# lambda_bl49_v7.net
KiCad netlist of a schematic drawn in EAGLE
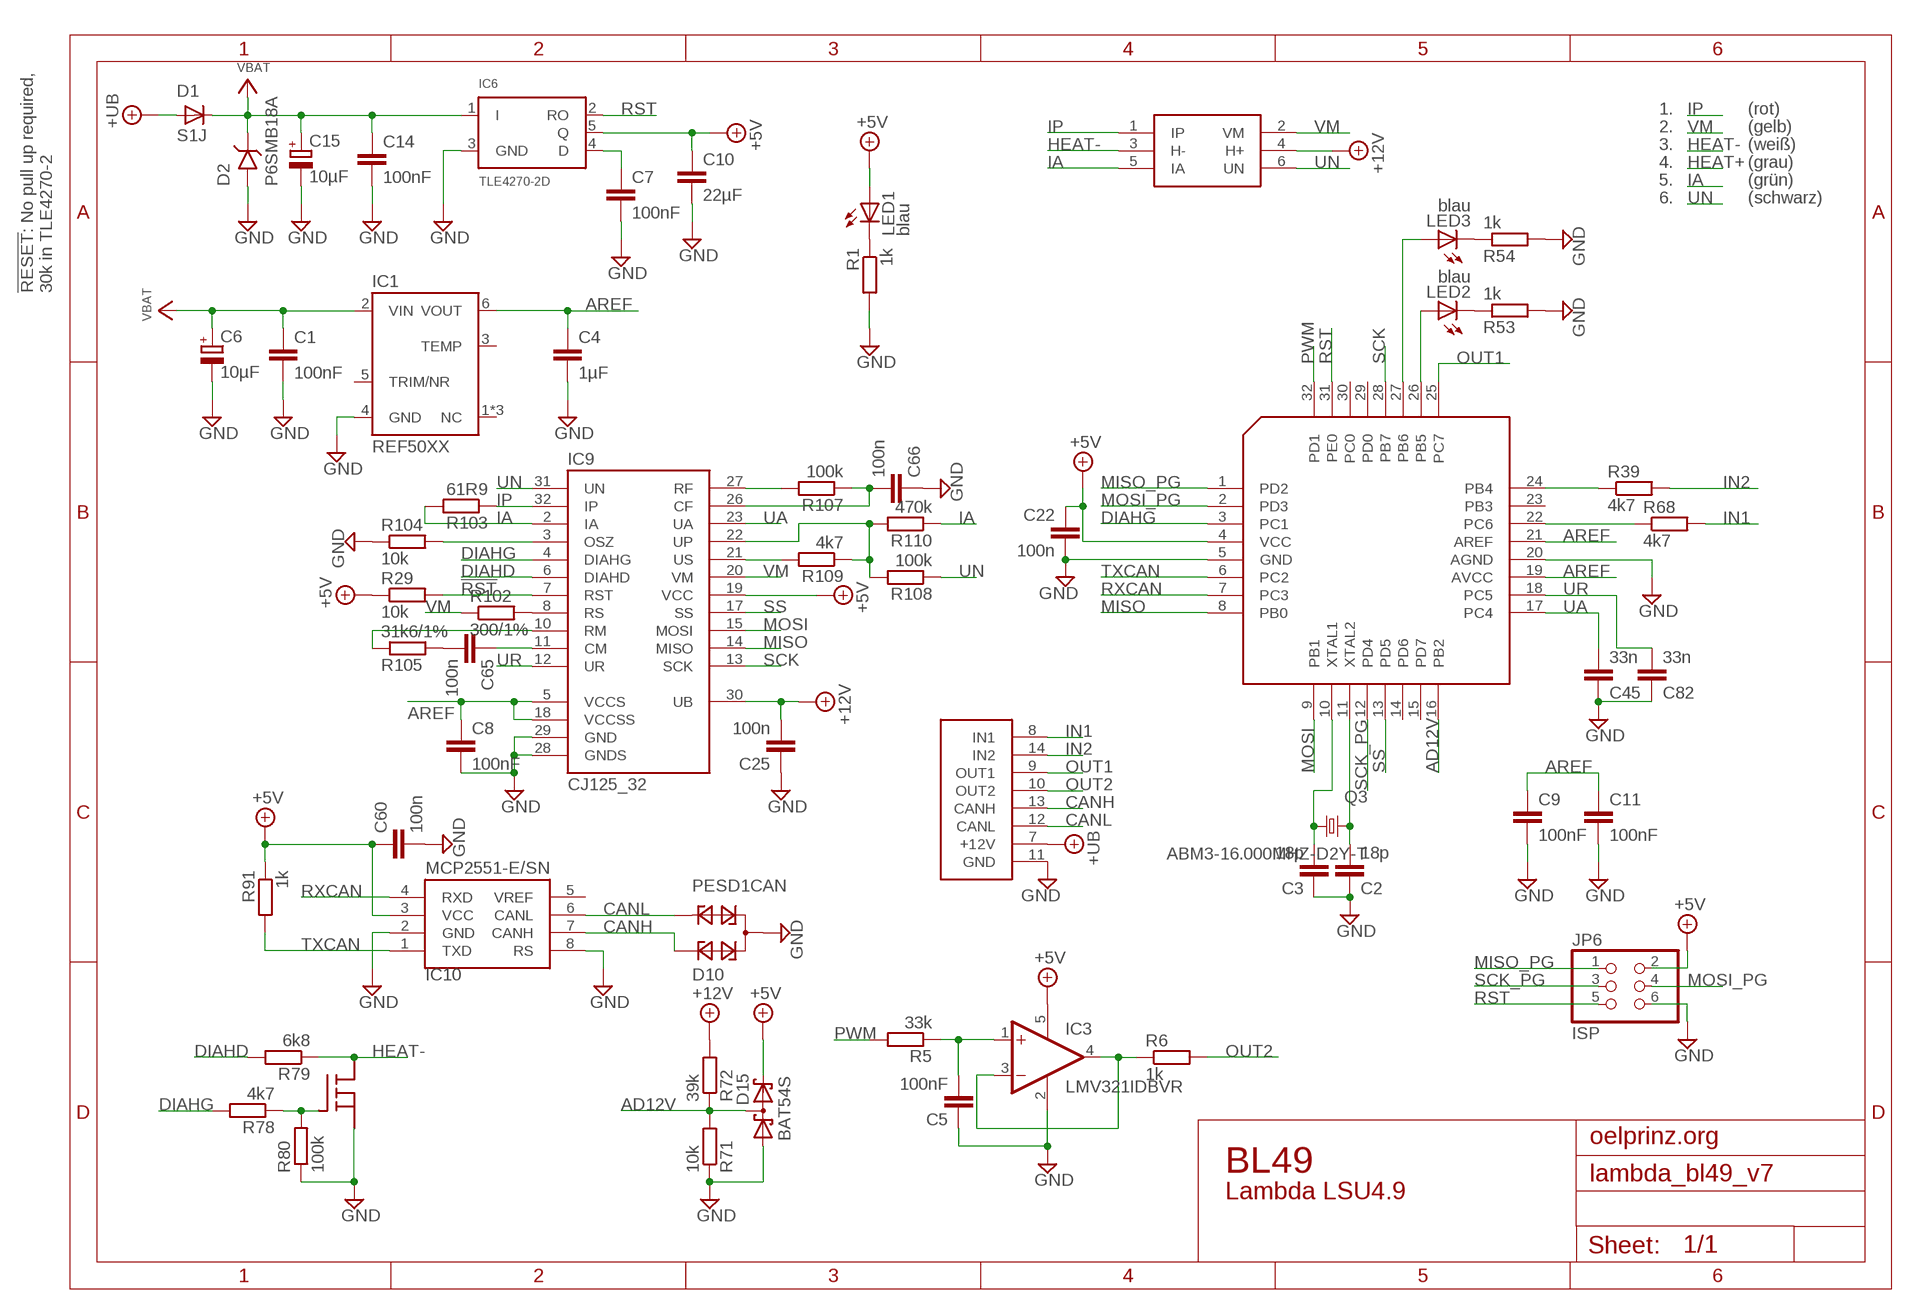
[diagram p0: schematic, sheet 1]

(export (version "E")
  (design (tool "Eeschema 10.0.6"))
  (components
    (comp (ref "C1")
      (value "100nF")
      (footprint "eagle-import:C0603")
      (libsource (lib "eagle-import") (part "rcl@1_C-EUC0603"))
    )
    (comp (ref "C2")
      (value "18p")
      (footprint "eagle-import:C0603")
      (libsource (lib "eagle-import") (part "C-EUC0603"))
    )
    (comp (ref "C3")
      (value "18p")
      (footprint "eagle-import:C0603")
      (libsource (lib "eagle-import") (part "C-EUC0603"))
    )
    (comp (ref "C4")
      (value "1µF")
      (footprint "eagle-import:C0603")
      (libsource (lib "eagle-import") (part "rcl@1_C-EUC0603"))
    )
    (comp (ref "C5")
      (value "100nF")
      (footprint "eagle-import:C0603")
      (libsource (lib "eagle-import") (part "C-EUC0603"))
    )
    (comp (ref "C6")
      (value "10µF")
      (footprint "eagle-import:PANASONIC_D")
      (libsource (lib "eagle-import") (part "CPOL-EUD"))
    )
    (comp (ref "C7")
      (value "100nF")
      (footprint "eagle-import:C0603")
      (libsource (lib "eagle-import") (part "rcl@1_C-EUC0603"))
    )
    (comp (ref "C8")
      (value "100nF")
      (footprint "eagle-import:C0603")
      (libsource (lib "eagle-import") (part "rcl@1_C-EUC0603"))
    )
    (comp (ref "C9")
      (value "100nF")
      (footprint "eagle-import:C0603")
      (libsource (lib "eagle-import") (part "rcl@1_C-EUC0603"))
    )
    (comp (ref "C10")
      (value "22µF")
      (footprint "eagle-import:C1206")
      (libsource (lib "eagle-import") (part "rcl@1_C-EUC1206"))
    )
    (comp (ref "C11")
      (value "100nF")
      (footprint "eagle-import:C0603")
      (libsource (lib "eagle-import") (part "rcl@1_C-EUC0603"))
    )
    (comp (ref "C14")
      (value "100nF")
      (footprint "eagle-import:C0603")
      (libsource (lib "eagle-import") (part "rcl@1_C-EUC0603"))
    )
    (comp (ref "C15")
      (value "10µF")
      (footprint "eagle-import:PANASONIC_D")
      (libsource (lib "eagle-import") (part "CPOL-EUD"))
    )
    (comp (ref "C22")
      (value "100n")
      (footprint "eagle-import:C0603")
      (libsource (lib "eagle-import") (part "C-EUC0603"))
    )
    (comp (ref "C25")
      (value "100n")
      (footprint "eagle-import:C0603")
      (libsource (lib "eagle-import") (part "rcl@1_C-EUC0603"))
    )
    (comp (ref "C45")
      (value "33n")
      (footprint "eagle-import:C0603")
      (libsource (lib "eagle-import") (part "C-EUC0603"))
    )
    (comp (ref "C60")
      (value "100n")
      (footprint "eagle-import:C0603")
      (libsource (lib "eagle-import") (part "C-EUC0603"))
    )
    (comp (ref "C65")
      (value "100n")
      (footprint "eagle-import:C0603")
      (libsource (lib "eagle-import") (part "C-EUC0603"))
    )
    (comp (ref "C66")
      (value "100n")
      (footprint "eagle-import:C0603")
      (libsource (lib "eagle-import") (part "C-EUC0603"))
    )
    (comp (ref "C82")
      (value "33n")
      (footprint "eagle-import:C0603")
      (libsource (lib "eagle-import") (part "C-EUC0603"))
    )
    (comp (ref "D1")
      (value "S1J")
      (footprint "eagle-import:SMADIODE")
      (libsource (lib "eagle-import") (part "DIODESMA"))
    )
    (comp (ref "D2")
      (value "P6SMB18A")
      (footprint "eagle-import:DO-214AA")
      (libsource (lib "eagle-import") (part "P6SMBXXASMB"))
    )
    (comp (ref "D10")
      (value "PESD1CAN")
      (footprint "eagle-import:SOT23")
      (libsource (lib "eagle-import") (part "PESD1CAN"))
    )
    (comp (ref "D15")
      (value "BAT54S")
      (footprint "eagle-import:SOT23")
      (libsource (lib "eagle-import") (part "BAT54S"))
    )
    (comp (ref "IC1")
      (value "REF50XX")
      (footprint "eagle-import:SOIC127P600X175-8N")
      (fields
        (field (name "MANUFACTURER_PART_NUMBER") "REF5050AIDR")
        (field (name "MOUSER_PART_NUMBER") "595-REF5050AIDR")
      )
      (libsource (lib "eagle-import") (part "REF50XX"))
    )
    (comp (ref "IC3")
      (value "LMV321IDBVR")
      (footprint "eagle-import:SC70-5L")
      (libsource (lib "eagle-import") (part "LMV321?M7"))
    )
    (comp (ref "IC6")
      (value "TLE4270-2D")
      (footprint "eagle-import:TO252-51")
      (libsource (lib "eagle-import") (part "TLE4270-2D"))
    )
    (comp (ref "IC9")
      (value "CJ125_32")
      (footprint "eagle-import:TQFP32-08")
      (libsource (lib "eagle-import") (part "CJ125_32"))
    )
    (comp (ref "IC10")
      (value "MCP2551-E/SN")
      (footprint "eagle-import:SOIC8")
      (libsource (lib "eagle-import") (part "MCP255"))
    )
    (comp (ref "JP6")
      (value "ISP")
      (footprint "eagle-import:2X03")
      (libsource (lib "eagle-import") (part "PINHD-2X3"))
    )
    (comp (ref "LED1")
      (value "blau")
      (footprint "eagle-import:SML0805")
      (libsource (lib "eagle-import") (part "LEDSML0805"))
    )
    (comp (ref "LED2")
      (value "blau")
      (footprint "eagle-import:SML0805")
      (libsource (lib "eagle-import") (part "LEDSML0805"))
    )
    (comp (ref "LED3")
      (value "blau")
      (footprint "eagle-import:SML0805")
      (libsource (lib "eagle-import") (part "LEDSML0805"))
    )
    (comp (ref "Q3")
      (value "ABM3-16.000MHZ-D2Y-T")
      (footprint "eagle-import:ABM3")
      (libsource (lib "eagle-import") (part "ABM3-8.000MHZ-D2Y-T"))
    )
    (comp (ref "R1")
      (value "1k")
      (footprint "eagle-import:R0603")
      (libsource (lib "eagle-import") (part "R-EU_R0603"))
    )
    (comp (ref "R5")
      (value "33k")
      (footprint "eagle-import:R0603")
      (libsource (lib "eagle-import") (part "R-EU_R0603"))
    )
    (comp (ref "R6")
      (value "1k")
      (footprint "eagle-import:R0603")
      (libsource (lib "eagle-import") (part "R-EU_R0603"))
    )
    (comp (ref "R29")
      (value "10k")
      (footprint "eagle-import:R0603")
      (libsource (lib "eagle-import") (part "R-EU_R0603"))
    )
    (comp (ref "R39")
      (value "4k7")
      (footprint "eagle-import:R0603")
      (libsource (lib "eagle-import") (part "R-EU_R0603"))
    )
    (comp (ref "R53")
      (value "1k")
      (footprint "eagle-import:R0603")
      (libsource (lib "eagle-import") (part "R-EU_R0603"))
    )
    (comp (ref "R54")
      (value "1k")
      (footprint "eagle-import:R0603")
      (libsource (lib "eagle-import") (part "R-EU_R0603"))
    )
    (comp (ref "R68")
      (value "4k7")
      (footprint "eagle-import:R0603")
      (libsource (lib "eagle-import") (part "R-EU_R0603"))
    )
    (comp (ref "R71")
      (value "10k")
      (footprint "eagle-import:R0603")
      (libsource (lib "eagle-import") (part "R-EU_R0603"))
    )
    (comp (ref "R72")
      (value "39k")
      (footprint "eagle-import:R0603")
      (libsource (lib "eagle-import") (part "R-EU_R0603"))
    )
    (comp (ref "R78")
      (value "4k7")
      (footprint "eagle-import:R0603")
      (libsource (lib "eagle-import") (part "R-EU_R0603"))
    )
    (comp (ref "R79")
      (value "6k8")
      (footprint "eagle-import:R0603")
      (libsource (lib "eagle-import") (part "R-EU_R0603"))
    )
    (comp (ref "R80")
      (value "100k")
      (footprint "eagle-import:R0603")
      (libsource (lib "eagle-import") (part "R-EU_R0603"))
    )
    (comp (ref "R91")
      (value "1k")
      (footprint "eagle-import:R0603")
      (libsource (lib "eagle-import") (part "R-EU_R0603"))
    )
    (comp (ref "R102")
      (value "300/1%")
      (footprint "eagle-import:R0603")
      (libsource (lib "eagle-import") (part "R-EU_R0603"))
    )
    (comp (ref "R103")
      (value "61R9")
      (footprint "eagle-import:R0603")
      (libsource (lib "eagle-import") (part "R-EU_R0603"))
    )
    (comp (ref "R104")
      (value "10k")
      (footprint "eagle-import:R0603")
      (libsource (lib "eagle-import") (part "R-EU_R0603"))
    )
    (comp (ref "R105")
      (value "31k6/1%")
      (footprint "eagle-import:R0603")
      (libsource (lib "eagle-import") (part "R-EU_R0603"))
    )
    (comp (ref "R107")
      (value "100k")
      (footprint "eagle-import:R0603")
      (libsource (lib "eagle-import") (part "R-EU_R0603"))
    )
    (comp (ref "R108")
      (value "100k")
      (footprint "eagle-import:R0603")
      (libsource (lib "eagle-import") (part "R-EU_R0603"))
    )
    (comp (ref "R109")
      (value "4k7")
      (footprint "eagle-import:R0603")
      (libsource (lib "eagle-import") (part "R-EU_R0603"))
    )
    (comp (ref "R110")
      (value "470k")
      (footprint "eagle-import:R0603")
      (libsource (lib "eagle-import") (part "R-EU_R0603"))
    )
    (comp (ref "U$1")
      (value "BL49")
      (footprint "eagle-import:BL49")
      (libsource (lib "eagle-import") (part "BL49"))
    )
    (comp (ref "U$2")
      (value "ATMEGA32M1-AU")
      (footprint "eagle-import:TQFP32-08")
      (libsource (lib "eagle-import") (part "AT32M1"))
    )
    (comp (ref "U$3")
      (value "STD30NF06LT4")
      (footprint "eagle-import:DPACK_2")
      (libsource (lib "eagle-import") (part "IRLZ44"))
    )
  )
  (nets
    (net (code "1") (name "+5V") (class "Default")
      (node (ref "C10") (pin "1") (pinfunction "1_1") (pintype "passive"))
      (node (ref "C22") (pin "1") (pinfunction "1_1") (pintype "passive"))
      (node (ref "C60") (pin "1") (pinfunction "1_1") (pintype "passive"))
      (node (ref "D15") (pin "2") (pinfunction "C2_2") (pintype "passive"))
      (node (ref "IC10") (pin "3") (pinfunction "VCC_3") (pintype "bidirectional"))
      (node (ref "IC3") (pin "5") (pinfunction "V+_5") (pintype "power_in"))
      (node (ref "IC6") (pin "5") (pinfunction "Q_5") (pintype "bidirectional"))
      (node (ref "IC9") (pin "19") (pinfunction "VCC_19") (pintype "bidirectional"))
      (node (ref "JP6") (pin "2") (pinfunction "2_2") (pintype "passive"))
      (node (ref "LED1") (pin "A") (pinfunction "A_A") (pintype "passive"))
      (node (ref "R29") (pin "1") (pinfunction "1_1") (pintype "passive"))
      (node (ref "R91") (pin "1") (pinfunction "1_1") (pintype "passive"))
      (node (ref "U$2") (pin "4") (pinfunction "VCC_4") (pintype "bidirectional"))
    )
    (net (code "2") (name "+12V") (class "Default")
      (node (ref "C25") (pin "2") (pinfunction "2_2") (pintype "passive"))
      (node (ref "IC9") (pin "30") (pinfunction "UB_30") (pintype "bidirectional"))
      (node (ref "R72") (pin "2") (pinfunction "2_2") (pintype "passive"))
      (node (ref "U$1") (pin "4") (pinfunction "H+_4") (pintype "bidirectional"))
    )
    (net (code "3") (name "+UB") (class "Default")
      (node (ref "D1") (pin "A") (pinfunction "A_A") (pintype "passive"))
      (node (ref "U$1") (pin "7") (pinfunction "+12V_7") (pintype "bidirectional"))
    )
    (net (code "4") (name "/AD12V") (class "Default")
      (node (ref "D15") (pin "3") (pinfunction "C1A2_3") (pintype "passive"))
      (node (ref "R71") (pin "2") (pinfunction "2_2") (pintype "passive"))
      (node (ref "R72") (pin "1") (pinfunction "1_1") (pintype "passive"))
      (node (ref "U$2") (pin "16") (pinfunction "PB2_16") (pintype "bidirectional"))
    )
    (net (code "5") (name "/AREF") (class "Default")
      (node (ref "C11") (pin "1") (pinfunction "1_1") (pintype "passive"))
      (node (ref "C4") (pin "1") (pinfunction "1_1") (pintype "passive"))
      (node (ref "C8") (pin "1") (pinfunction "1_1") (pintype "passive"))
      (node (ref "C9") (pin "1") (pinfunction "1_1") (pintype "passive"))
      (node (ref "IC1") (pin "6") (pinfunction "VOUT_6") (pintype "output"))
      (node (ref "IC9") (pin "18") (pinfunction "VCCSS_18") (pintype "bidirectional"))
      (node (ref "IC9") (pin "5") (pinfunction "VCCS_5") (pintype "bidirectional"))
      (node (ref "U$2") (pin "19") (pinfunction "AVCC_19") (pintype "bidirectional"))
      (node (ref "U$2") (pin "21") (pinfunction "AREF_21") (pintype "bidirectional"))
    )
    (net (code "6") (name "/CANH") (class "Default")
      (node (ref "D10") (pin "1") (pinfunction "1_1") (pintype "passive"))
      (node (ref "IC10") (pin "7") (pinfunction "CANH_7") (pintype "bidirectional"))
      (node (ref "U$1") (pin "13") (pinfunction "CANH_13") (pintype "bidirectional"))
    )
    (net (code "7") (name "/CANL") (class "Default")
      (node (ref "D10") (pin "2") (pinfunction "2_2") (pintype "passive"))
      (node (ref "IC10") (pin "6") (pinfunction "CANL_6") (pintype "bidirectional"))
      (node (ref "U$1") (pin "12") (pinfunction "CANL_12") (pintype "bidirectional"))
    )
    (net (code "8") (name "/DIAHD") (class "Default")
      (node (ref "IC9") (pin "6") (pinfunction "DIAHD_6") (pintype "bidirectional"))
      (node (ref "R79") (pin "2") (pinfunction "2_2") (pintype "passive"))
    )
    (net (code "9") (name "/DIAHG") (class "Default")
      (node (ref "IC9") (pin "4") (pinfunction "DIAHG_4") (pintype "bidirectional"))
      (node (ref "R78") (pin "2") (pinfunction "2_2") (pintype "passive"))
      (node (ref "U$2") (pin "3") (pinfunction "PC1_3") (pintype "bidirectional"))
    )
    (net (code "11") (name "/HEAT-") (class "Default")
      (node (ref "R79") (pin "1") (pinfunction "1_1") (pintype "passive"))
      (node (ref "U$1") (pin "3") (pinfunction "H-_3") (pintype "bidirectional"))
      (node (ref "U$3") (pin "D") (pinfunction "2_D") (pintype "bidirectional"))
    )
    (net (code "12") (name "/IA") (class "Default")
      (node (ref "IC9") (pin "2") (pinfunction "IA_2") (pintype "bidirectional"))
      (node (ref "R103") (pin "2") (pinfunction "2_2") (pintype "passive"))
      (node (ref "R110") (pin "1") (pinfunction "1_1") (pintype "passive"))
      (node (ref "U$1") (pin "5") (pinfunction "IA_5") (pintype "bidirectional"))
    )
    (net (code "13") (name "/IN1") (class "Default")
      (node (ref "R68") (pin "2") (pinfunction "2_2") (pintype "passive"))
      (node (ref "U$1") (pin "8") (pinfunction "IN1_8") (pintype "bidirectional"))
    )
    (net (code "14") (name "/IN2") (class "Default")
      (node (ref "R39") (pin "2") (pinfunction "2_2") (pintype "passive"))
      (node (ref "U$1") (pin "14") (pinfunction "IN2_14") (pintype "bidirectional"))
    )
    (net (code "15") (name "/IP") (class "Default")
      (node (ref "IC9") (pin "32") (pinfunction "IP_32") (pintype "bidirectional"))
      (node (ref "R103") (pin "1") (pinfunction "1_1") (pintype "passive"))
      (node (ref "U$1") (pin "1") (pinfunction "IP_1") (pintype "bidirectional"))
    )
    (net (code "16") (name "/MISO") (class "Default")
      (node (ref "IC9") (pin "14") (pinfunction "MISO_14") (pintype "bidirectional"))
      (node (ref "U$2") (pin "8") (pinfunction "PB0_8") (pintype "bidirectional"))
    )
    (net (code "17") (name "/MISO_PG") (class "Default")
      (node (ref "JP6") (pin "1") (pinfunction "1_1") (pintype "passive"))
      (node (ref "U$2") (pin "1") (pinfunction "PD2_1") (pintype "bidirectional"))
    )
    (net (code "18") (name "/MOSI") (class "Default")
      (node (ref "IC9") (pin "15") (pinfunction "MOSI_15") (pintype "bidirectional"))
      (node (ref "U$2") (pin "9") (pinfunction "PB1_9") (pintype "bidirectional"))
    )
    (net (code "19") (name "/MOSI_PG") (class "Default")
      (node (ref "JP6") (pin "4") (pinfunction "4_4") (pintype "passive"))
      (node (ref "U$2") (pin "2") (pinfunction "PD3_2") (pintype "bidirectional"))
    )
    (net (code "20") (name "/OUT1") (class "Default")
      (node (ref "U$1") (pin "9") (pinfunction "OUT1_9") (pintype "bidirectional"))
      (node (ref "U$2") (pin "25") (pinfunction "PC7_25") (pintype "bidirectional"))
    )
    (net (code "21") (name "/OUT2") (class "Default")
      (node (ref "R6") (pin "2") (pinfunction "2_2") (pintype "passive"))
      (node (ref "U$1") (pin "10") (pinfunction "OUT2_10") (pintype "bidirectional"))
    )
    (net (code "22") (name "/PWM") (class "Default")
      (node (ref "R5") (pin "2") (pinfunction "2_2") (pintype "passive"))
      (node (ref "U$2") (pin "32") (pinfunction "PD1_32") (pintype "bidirectional"))
    )
    (net (code "23") (name "/RST") (class "Default")
      (node (ref "IC6") (pin "2") (pinfunction "RO_2") (pintype "bidirectional"))
      (node (ref "JP6") (pin "5") (pinfunction "5_5") (pintype "passive"))
      (node (ref "U$2") (pin "31") (pinfunction "PE0_31") (pintype "bidirectional"))
    )
    (net (code "24") (name "/RXCAN") (class "Default")
      (node (ref "IC10") (pin "4") (pinfunction "RXD_4") (pintype "bidirectional"))
      (node (ref "U$2") (pin "7") (pinfunction "PC3_7") (pintype "bidirectional"))
    )
    (net (code "25") (name "/SCK") (class "Default")
      (node (ref "IC9") (pin "13") (pinfunction "SCK_13") (pintype "bidirectional"))
      (node (ref "U$2") (pin "28") (pinfunction "PB7_28") (pintype "bidirectional"))
    )
    (net (code "26") (name "/SCK_PG") (class "Default")
      (node (ref "JP6") (pin "3") (pinfunction "3_3") (pintype "passive"))
      (node (ref "U$2") (pin "12") (pinfunction "PD4_12") (pintype "bidirectional"))
    )
    (net (code "27") (name "/SS") (class "Default")
      (node (ref "IC9") (pin "17") (pinfunction "SS_17") (pintype "bidirectional"))
      (node (ref "U$2") (pin "13") (pinfunction "PD5_13") (pintype "bidirectional"))
    )
    (net (code "28") (name "/TXCAN") (class "Default")
      (node (ref "IC10") (pin "1") (pinfunction "TXD_1") (pintype "bidirectional"))
      (node (ref "R91") (pin "2") (pinfunction "2_2") (pintype "passive"))
      (node (ref "U$2") (pin "6") (pinfunction "PC2_6") (pintype "bidirectional"))
    )
    (net (code "29") (name "/UA") (class "Default")
      (node (ref "C45") (pin "2") (pinfunction "2_2") (pintype "passive"))
      (node (ref "IC9") (pin "23") (pinfunction "UA_23") (pintype "bidirectional"))
      (node (ref "U$2") (pin "17") (pinfunction "PC4_17") (pintype "bidirectional"))
    )
    (net (code "30") (name "/UN") (class "Default")
      (node (ref "IC9") (pin "31") (pinfunction "UN_31") (pintype "bidirectional"))
      (node (ref "R108") (pin "1") (pinfunction "1_1") (pintype "passive"))
      (node (ref "U$1") (pin "6") (pinfunction "UN_6") (pintype "bidirectional"))
    )
    (net (code "31") (name "/UR") (class "Default")
      (node (ref "C82") (pin "2") (pinfunction "2_2") (pintype "passive"))
      (node (ref "IC9") (pin "12") (pinfunction "UR_12") (pintype "bidirectional"))
      (node (ref "U$2") (pin "18") (pinfunction "PC5_18") (pintype "bidirectional"))
    )
    (net (code "32") (name "/VM") (class "Default")
      (node (ref "IC9") (pin "20") (pinfunction "VM_20") (pintype "bidirectional"))
      (node (ref "R102") (pin "1") (pinfunction "1_1") (pintype "passive"))
      (node (ref "U$1") (pin "2") (pinfunction "VM_2") (pintype "bidirectional"))
    )
    (net (code "33") (name "/~{RST}") (class "Default")
      (node (ref "IC9") (pin "7") (pinfunction "RST_7") (pintype "bidirectional"))
      (node (ref "R29") (pin "2") (pinfunction "2_2") (pintype "passive"))
    )
    (net (code "34") (name "GND") (class "Default")
      (node (ref "C1") (pin "2") (pinfunction "2_2") (pintype "passive"))
      (node (ref "C10") (pin "2") (pinfunction "2_2") (pintype "passive"))
      (node (ref "C11") (pin "2") (pinfunction "2_2") (pintype "passive"))
      (node (ref "C14") (pin "2") (pinfunction "2_2") (pintype "passive"))
      (node (ref "C15") (pin "-") (pinfunction "-_-") (pintype "passive"))
      (node (ref "C2") (pin "1") (pinfunction "1_1") (pintype "passive"))
      (node (ref "C22") (pin "2") (pinfunction "2_2") (pintype "passive"))
      (node (ref "C25") (pin "1") (pinfunction "1_1") (pintype "passive"))
      (node (ref "C3") (pin "1") (pinfunction "1_1") (pintype "passive"))
      (node (ref "C4") (pin "2") (pinfunction "2_2") (pintype "passive"))
      (node (ref "C45") (pin "1") (pinfunction "1_1") (pintype "passive"))
      (node (ref "C5") (pin "1") (pinfunction "1_1") (pintype "passive"))
      (node (ref "C6") (pin "-") (pinfunction "-_-") (pintype "passive"))
      (node (ref "C60") (pin "2") (pinfunction "2_2") (pintype "passive"))
      (node (ref "C66") (pin "1") (pinfunction "1_1") (pintype "passive"))
      (node (ref "C7") (pin "2") (pinfunction "2_2") (pintype "passive"))
      (node (ref "C8") (pin "2") (pinfunction "2_2") (pintype "passive"))
      (node (ref "C82") (pin "1") (pinfunction "1_1") (pintype "passive"))
      (node (ref "C9") (pin "2") (pinfunction "2_2") (pintype "passive"))
      (node (ref "D10") (pin "3") (pinfunction "3_3") (pintype "passive"))
      (node (ref "D15") (pin "1") (pinfunction "A1_1") (pintype "passive"))
      (node (ref "D2") (pin "P$2") (pinfunction "A_P$2") (pintype "passive"))
      (node (ref "IC1") (pin "4") (pinfunction "GND_4") (pintype "power_in"))
      (node (ref "IC10") (pin "2") (pinfunction "GND_2") (pintype "bidirectional"))
      (node (ref "IC10") (pin "8") (pinfunction "RS_8") (pintype "bidirectional"))
      (node (ref "IC3") (pin "2") (pinfunction "V-_2") (pintype "power_in"))
      (node (ref "IC6") (pin "3") (pinfunction "GND_3") (pintype "bidirectional"))
      (node (ref "IC9") (pin "28") (pinfunction "GNDS_28") (pintype "bidirectional"))
      (node (ref "IC9") (pin "29") (pinfunction "GND_29") (pintype "bidirectional"))
      (node (ref "JP6") (pin "6") (pinfunction "6_6") (pintype "passive"))
      (node (ref "R1") (pin "2") (pinfunction "2_2") (pintype "passive"))
      (node (ref "R104") (pin "1") (pinfunction "1_1") (pintype "passive"))
      (node (ref "R53") (pin "2") (pinfunction "2_2") (pintype "passive"))
      (node (ref "R54") (pin "2") (pinfunction "2_2") (pintype "passive"))
      (node (ref "R71") (pin "1") (pinfunction "1_1") (pintype "passive"))
      (node (ref "R80") (pin "1") (pinfunction "1_1") (pintype "passive"))
      (node (ref "U$1") (pin "11") (pinfunction "GND_11") (pintype "bidirectional"))
      (node (ref "U$2") (pin "20") (pinfunction "AGND_20") (pintype "bidirectional"))
      (node (ref "U$2") (pin "5") (pinfunction "GND_5") (pintype "bidirectional"))
      (node (ref "U$3") (pin "S") (pinfunction "3_S") (pintype "bidirectional"))
    )
    (net (code "35") (name "Net-(C65-Pad2)") (class "Default")
      (node (ref "C65") (pin "2") (pinfunction "2_2") (pintype "passive"))
      (node (ref "R105") (pin "2") (pinfunction "2_2") (pintype "passive"))
    )
    (net (code "36") (name "Net-(IC3-+IN)") (class "Default")
      (node (ref "C5") (pin "2") (pinfunction "2_2") (pintype "passive"))
      (node (ref "IC3") (pin "1") (pinfunction "+IN_1") (pintype "input"))
      (node (ref "R5") (pin "1") (pinfunction "1_1") (pintype "passive"))
    )
    (net (code "37") (name "Net-(IC3--IN)") (class "Default")
      (node (ref "IC3") (pin "3") (pinfunction "-IN_3") (pintype "input"))
      (node (ref "IC3") (pin "4") (pinfunction "OUT_4") (pintype "output"))
      (node (ref "R6") (pin "1") (pinfunction "1_1") (pintype "passive"))
    )
    (net (code "38") (name "Net-(IC6-D)") (class "Default")
      (node (ref "C7") (pin "1") (pinfunction "1_1") (pintype "passive"))
      (node (ref "IC6") (pin "4") (pinfunction "D_4") (pintype "bidirectional"))
    )
    (net (code "39") (name "Net-(IC9-CF)") (class "Default")
      (node (ref "C66") (pin "2") (pinfunction "2_2") (pintype "passive"))
      (node (ref "IC9") (pin "26") (pinfunction "CF_26") (pintype "bidirectional"))
      (node (ref "R107") (pin "1") (pinfunction "1_1") (pintype "passive"))
    )
    (net (code "40") (name "Net-(IC9-CM)") (class "Default")
      (node (ref "C65") (pin "1") (pinfunction "1_1") (pintype "passive"))
      (node (ref "IC9") (pin "11") (pinfunction "CM_11") (pintype "bidirectional"))
    )
    (net (code "41") (name "Net-(IC9-OSZ)") (class "Default")
      (node (ref "IC9") (pin "3") (pinfunction "OSZ_3") (pintype "bidirectional"))
      (node (ref "R104") (pin "2") (pinfunction "2_2") (pintype "passive"))
    )
    (net (code "42") (name "Net-(IC9-RF)") (class "Default")
      (node (ref "IC9") (pin "27") (pinfunction "RF_27") (pintype "bidirectional"))
      (node (ref "R107") (pin "2") (pinfunction "2_2") (pintype "passive"))
    )
    (net (code "43") (name "Net-(IC9-RM)") (class "Default")
      (node (ref "IC9") (pin "10") (pinfunction "RM_10") (pintype "bidirectional"))
      (node (ref "R105") (pin "1") (pinfunction "1_1") (pintype "passive"))
    )
    (net (code "44") (name "Net-(IC9-RS)") (class "Default")
      (node (ref "IC9") (pin "8") (pinfunction "RS_8") (pintype "bidirectional"))
      (node (ref "R102") (pin "2") (pinfunction "2_2") (pintype "passive"))
    )
    (net (code "45") (name "Net-(IC9-UP)") (class "Default")
      (node (ref "IC9") (pin "22") (pinfunction "UP_22") (pintype "bidirectional"))
      (node (ref "R108") (pin "2") (pinfunction "2_2") (pintype "passive"))
      (node (ref "R109") (pin "1") (pinfunction "1_1") (pintype "passive"))
      (node (ref "R110") (pin "2") (pinfunction "2_2") (pintype "passive"))
    )
    (net (code "46") (name "Net-(IC9-US)") (class "Default")
      (node (ref "IC9") (pin "21") (pinfunction "US_21") (pintype "bidirectional"))
      (node (ref "R109") (pin "2") (pinfunction "2_2") (pintype "passive"))
    )
    (net (code "47") (name "Net-(LED1-PadC)") (class "Default")
      (node (ref "LED1") (pin "C") (pinfunction "C_C") (pintype "passive"))
      (node (ref "R1") (pin "1") (pinfunction "1_1") (pintype "passive"))
    )
    (net (code "48") (name "Net-(LED2-PadC)") (class "Default")
      (node (ref "LED2") (pin "C") (pinfunction "C_C") (pintype "passive"))
      (node (ref "R53") (pin "1") (pinfunction "1_1") (pintype "passive"))
    )
    (net (code "49") (name "Net-(LED3-PadC)") (class "Default")
      (node (ref "LED3") (pin "C") (pinfunction "C_C") (pintype "passive"))
      (node (ref "R54") (pin "1") (pinfunction "1_1") (pintype "passive"))
    )
    (net (code "50") (name "Net-(U$2-PB4)") (class "Default")
      (node (ref "R39") (pin "1") (pinfunction "1_1") (pintype "passive"))
      (node (ref "U$2") (pin "24") (pinfunction "PB4_24") (pintype "bidirectional"))
    )
    (net (code "51") (name "Net-(U$2-PB5)") (class "Default")
      (node (ref "LED2") (pin "A") (pinfunction "A_A") (pintype "passive"))
      (node (ref "U$2") (pin "26") (pinfunction "PB5_26") (pintype "bidirectional"))
    )
    (net (code "52") (name "Net-(U$2-PB6)") (class "Default")
      (node (ref "LED3") (pin "A") (pinfunction "A_A") (pintype "passive"))
      (node (ref "U$2") (pin "27") (pinfunction "PB6_27") (pintype "bidirectional"))
    )
    (net (code "53") (name "Net-(U$2-PC6)") (class "Default")
      (node (ref "R68") (pin "1") (pinfunction "1_1") (pintype "passive"))
      (node (ref "U$2") (pin "22") (pinfunction "PC6_22") (pintype "bidirectional"))
    )
    (net (code "54") (name "Net-(U$2-XTAL1)") (class "Default")
      (node (ref "C3") (pin "2") (pinfunction "2_2") (pintype "passive"))
      (node (ref "Q3") (pin "2") (pinfunction "2_2") (pintype "bidirectional"))
      (node (ref "U$2") (pin "10") (pinfunction "XTAL1_10") (pintype "bidirectional"))
    )
    (net (code "55") (name "Net-(U$2-XTAL2)") (class "Default")
      (node (ref "C2") (pin "2") (pinfunction "2_2") (pintype "passive"))
      (node (ref "Q3") (pin "1") (pinfunction "1_1") (pintype "bidirectional"))
      (node (ref "U$2") (pin "11") (pinfunction "XTAL2_11") (pintype "bidirectional"))
    )
    (net (code "56") (name "Net-(U$3-1)") (class "Default")
      (node (ref "R78") (pin "1") (pinfunction "1_1") (pintype "passive"))
      (node (ref "R80") (pin "2") (pinfunction "2_2") (pintype "passive"))
      (node (ref "U$3") (pin "G") (pinfunction "1_G") (pintype "bidirectional"))
    )
    (net (code "57") (name "VBAT") (class "Default")
      (node (ref "C1") (pin "1") (pinfunction "1_1") (pintype "passive"))
      (node (ref "C14") (pin "1") (pinfunction "1_1") (pintype "passive"))
      (node (ref "C15") (pin "+") (pinfunction "+_+") (pintype "passive"))
      (node (ref "C6") (pin "+") (pinfunction "+_+") (pintype "passive"))
      (node (ref "D1") (pin "C") (pinfunction "C_C") (pintype "passive"))
      (node (ref "D2") (pin "P$1") (pinfunction "C_P$1") (pintype "passive"))
      (node (ref "IC1") (pin "2") (pinfunction "VIN_2") (pintype "power_in"))
      (node (ref "IC6") (pin "1") (pinfunction "I_1") (pintype "bidirectional"))
    )
    (net (code "58") (name "unconnected-(IC1-NC-Pad1)") (class "Default")
      (node (ref "IC1") (pin "1") (pinfunction "NC_1") (pintype "no_connect"))
    )
    (net (code "59") (name "unconnected-(IC1-NC-Pad7)") (class "Default")
      (node (ref "IC1") (pin "7") (pinfunction "NC_7") (pintype "no_connect"))
    )
    (net (code "60") (name "unconnected-(IC1-NC-Pad8)") (class "Default")
      (node (ref "IC1") (pin "8") (pinfunction "NC_8") (pintype "no_connect"))
    )
    (net (code "61") (name "unconnected-(IC1-TEMP-Pad3)") (class "Default")
      (node (ref "IC1") (pin "3") (pinfunction "TEMP_3") (pintype "input"))
    )
    (net (code "62") (name "unconnected-(IC1-TRIM{slash}NR-Pad5)") (class "Default")
      (node (ref "IC1") (pin "5") (pinfunction "TRIM/NR_5") (pintype "input"))
    )
    (net (code "63") (name "unconnected-(IC10-VREF-Pad5)") (class "Default")
      (node (ref "IC10") (pin "5") (pinfunction "VREF_5") (pintype "bidirectional"))
    )
    (net (code "64") (name "unconnected-(U$2-PB3-Pad23)") (class "Default")
      (node (ref "U$2") (pin "23") (pinfunction "PB3_23") (pintype "bidirectional"))
    )
    (net (code "65") (name "unconnected-(U$2-PC0-Pad30)") (class "Default")
      (node (ref "U$2") (pin "30") (pinfunction "PC0_30") (pintype "bidirectional"))
    )
    (net (code "66") (name "unconnected-(U$2-PD0-Pad29)") (class "Default")
      (node (ref "U$2") (pin "29") (pinfunction "PD0_29") (pintype "bidirectional"))
    )
    (net (code "67") (name "unconnected-(U$2-PD6-Pad14)") (class "Default")
      (node (ref "U$2") (pin "14") (pinfunction "PD6_14") (pintype "bidirectional"))
    )
    (net (code "68") (name "unconnected-(U$2-PD7-Pad15)") (class "Default")
      (node (ref "U$2") (pin "15") (pinfunction "PD7_15") (pintype "bidirectional"))
    )
  )
)
